# I2C-Magnetometer-sensor.net
KiCad netlist of a schematic drawn in Altium Designer
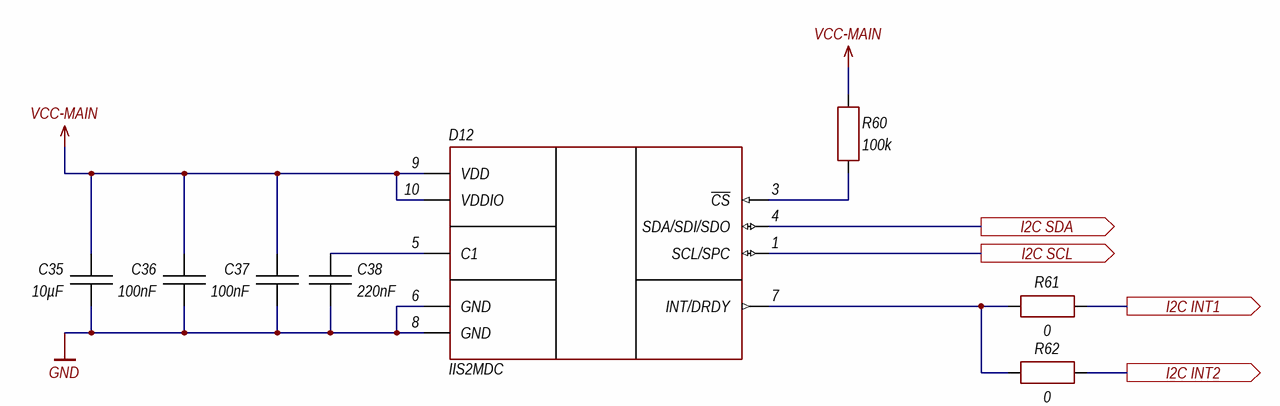
[diagram p0: I2C-Magnetometer-sensor.SchDoc]

(export (version "E")
  (design (tool "Eeschema 10.0.6"))
  (components
    (comp (ref "C35") (value "10µF") (footprint "CH0402C") (libsource (lib "Discrete") (part "Capacitor")))
    (comp (ref "C36") (value "100nF") (footprint "CH0402C") (libsource (lib "Discrete") (part "Capacitor")))
    (comp (ref "C37") (value "100nF") (footprint "CH0402C") (libsource (lib "Discrete") (part "Capacitor")))
    (comp (ref "C38") (value "220nF") (footprint "CH0402C") (libsource (lib "Discrete") (part "Capacitor")))
    (comp (ref "D12")
      (value "IIS2MDC")
      (footprint "12-LGA (2x2mm)")
      (description "3-axis magnetometer, I2C/SPI")
      (fields (field (name "MANUFACTURER") "STMicroelectronics"))
      (libsource (lib "Digital") (part "IIS2MDC"))
    )
    (comp (ref "R60") (value "100k") (footprint "CH0402R") (libsource (lib "") (part "Resistor_1")))
    (comp (ref "R61") (value "0") (footprint "CH0402R") (libsource (lib "Discrete") (part "Resistor")))
    (comp (ref "R62") (value "0") (footprint "CH0402R") (libsource (lib "Discrete") (part "Resistor")))
  )
  (nets
    (net (code "1") (name "/I2C INT1") (class "Default")
      (node (ref "R61") (pin "1") (pinfunction "1_1") (pintype "passive"))
    )
    (net (code "2") (name "/I2C INT2") (class "Default")
      (node (ref "R62") (pin "1") (pinfunction "1_1") (pintype "passive"))
    )
    (net (code "3") (name "/I2C SCL") (class "Default")
      (node (ref "D12") (pin "1") (pinfunction "SCL/SPC_1") (pintype "bidirectional"))
    )
    (net (code "4") (name "/I2C SDA") (class "Default")
      (node (ref "D12") (pin "4") (pinfunction "SDA/SDI/SDO_4") (pintype "bidirectional"))
    )
    (net (code "5") (name "GND") (class "Default")
      (node (ref "C35") (pin "1") (pinfunction "1_1") (pintype "passive"))
      (node (ref "C36") (pin "1") (pinfunction "1_1") (pintype "passive"))
      (node (ref "C37") (pin "1") (pinfunction "1_1") (pintype "passive"))
      (node (ref "C38") (pin "1") (pinfunction "1_1") (pintype "passive"))
      (node (ref "D12") (pin "6") (pinfunction "GND_6") (pintype "power_in"))
      (node (ref "D12") (pin "8") (pinfunction "GND_8") (pintype "power_in"))
    )
    (net (code "6") (name "Net-(D12-C1)") (class "Default")
      (node (ref "C38") (pin "2") (pinfunction "2_2") (pintype "passive"))
      (node (ref "D12") (pin "5") (pinfunction "C1_5") (pintype "passive"))
    )
    (net (code "7") (name "Net-(D12-INT{slash}DRDY)") (class "Default")
      (node (ref "D12") (pin "7") (pinfunction "INT/DRDY_7") (pintype "output"))
      (node (ref "R61") (pin "2") (pinfunction "2_2") (pintype "passive"))
      (node (ref "R62") (pin "2") (pinfunction "2_2") (pintype "passive"))
    )
    (net (code "8") (name "Net-(D12-~{CS})") (class "Default")
      (node (ref "D12") (pin "3") (pinfunction "~{CS}_3") (pintype "input"))
      (node (ref "R60") (pin "1") (pinfunction "1_1") (pintype "passive"))
    )
    (net (code "9") (name "VCC-MAIN") (class "Default")
      (node (ref "C35") (pin "2") (pinfunction "2_2") (pintype "passive"))
      (node (ref "C36") (pin "2") (pinfunction "2_2") (pintype "passive"))
      (node (ref "C37") (pin "2") (pinfunction "2_2") (pintype "passive"))
      (node (ref "D12") (pin "10") (pinfunction "VDDIO_10") (pintype "power_in"))
      (node (ref "D12") (pin "9") (pinfunction "VDD_9") (pintype "power_in"))
      (node (ref "R60") (pin "2") (pinfunction "2_2") (pintype "passive"))
    )
  )
)
